# Board3.net
KiCad netlist of a schematic drawn in Altium Designer
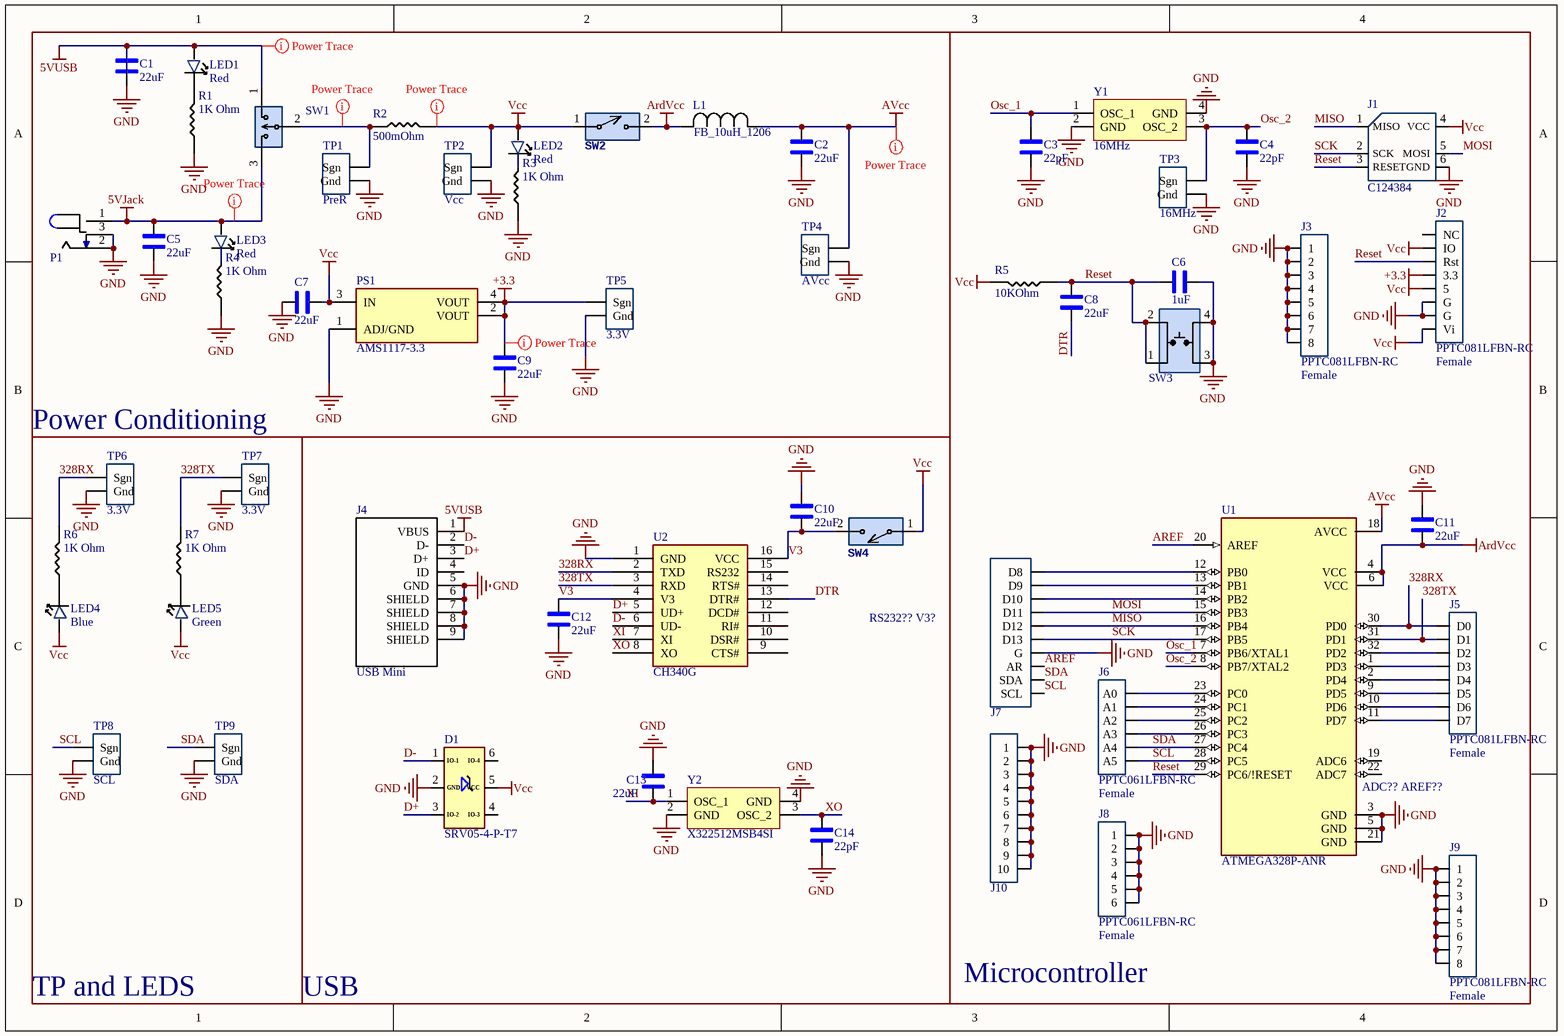
[diagram p0: Board3.SchDoc]

(export (version "E")
  (design (tool "Eeschema 10.0.6"))
  (components
    (comp (ref "C1")
      (value "22uF")
      (footprint "1206_Passive_Capacitor")
      (description "22uF ±10% 25V X5R 1206 Multilayer Ceramic Capacitors MLCC - SMD/SMT RoHS")
      (fields (field (name "MFR PART #") "CL31A226KAHNNNE") (field (name "LCSC PART#") "C12891"))
      (libsource (lib "ECEN5730Lib_2023_01_DS") (part "C_22uF_1206"))
    )
    (comp (ref "C2")
      (value "22uF")
      (footprint "1206_Passive_Capacitor")
      (description "22uF ±10% 25V X5R 1206 Multilayer Ceramic Capacitors MLCC - SMD/SMT RoHS")
      (fields (field (name "MFR PART #") "CL31A226KAHNNNE") (field (name "LCSC PART#") "C12891"))
      (libsource (lib "ECEN5730Lib_2023_01_DS") (part "C_22uF_1206"))
    )
    (comp (ref "C3")
      (value "22pF")
      (footprint "1206_Passive_Capacitor")
      (description "22pF ±5% 1kV C0G 1206 Multilayer Ceramic Capacitors MLCC - SMD/SMT RoHS")
      (fields (field (name "LCSC PART#") "C313096") (field (name "MFR PART #") "1206CG220J102NT"))
      (libsource (lib "ECEN5730Lib_2023_01_DS") (part "C_22pF_1206"))
    )
    (comp (ref "C4")
      (value "22pF")
      (footprint "1206_Passive_Capacitor")
      (description "22pF ±5% 1kV C0G 1206 Multilayer Ceramic Capacitors MLCC - SMD/SMT RoHS")
      (fields (field (name "LCSC PART#") "C313096") (field (name "MFR PART #") "1206CG220J102NT"))
      (libsource (lib "ECEN5730Lib_2023_01_DS") (part "C_22pF_1206"))
    )
    (comp (ref "C5")
      (value "22uF")
      (footprint "1206_Passive_Capacitor")
      (description "22uF ±10% 25V X5R 1206 Multilayer Ceramic Capacitors MLCC - SMD/SMT RoHS")
      (fields (field (name "MFR PART #") "CL31A226KAHNNNE") (field (name "LCSC PART#") "C12891"))
      (libsource (lib "ECEN5730Lib_2023_01_DS") (part "C_22uF_1206"))
    )
    (comp (ref "C6")
      (value "1uF")
      (footprint "1206_Passive_Capacitor")
      (description "MULTILAYER CERAMIC CAPACITORS MLCC - SMD/SMT 1UF 50V 1206 ROHS")
      (fields (field (name "MFR PART #") "CL31B105KBHNNNE") (field (name "LCSC PART#") "C1848"))
      (libsource (lib "ECEN5730Lib_2023_01_DS") (part "C_1uF_1206"))
    )
    (comp (ref "C7")
      (value "22uF")
      (footprint "1206_Passive_Capacitor")
      (description "22uF ±10% 25V X5R 1206 Multilayer Ceramic Capacitors MLCC - SMD/SMT RoHS")
      (fields (field (name "MFR PART #") "CL31A226KAHNNNE") (field (name "LCSC PART#") "C12891"))
      (libsource (lib "ECEN5730Lib_2023_01_DS") (part "C_22uF_1206"))
    )
    (comp (ref "C8")
      (value "22uF")
      (footprint "1206_Passive_Capacitor")
      (description "22uF ±10% 25V X5R 1206 Multilayer Ceramic Capacitors MLCC - SMD/SMT RoHS")
      (fields (field (name "MFR PART #") "CL31A226KAHNNNE") (field (name "LCSC PART#") "C12891"))
      (libsource (lib "ECEN5730Lib_2023_01_DS") (part "C_22uF_1206"))
    )
    (comp (ref "C9")
      (value "22uF")
      (footprint "1206_Passive_Capacitor")
      (description "22uF ±10% 25V X5R 1206 Multilayer Ceramic Capacitors MLCC - SMD/SMT RoHS")
      (fields (field (name "MFR PART #") "CL31A226KAHNNNE") (field (name "LCSC PART#") "C12891"))
      (libsource (lib "ECEN5730Lib_2023_01_DS") (part "C_22uF_1206"))
    )
    (comp (ref "C10")
      (value "22uF")
      (footprint "1206_Passive_Capacitor")
      (description "22uF ±10% 25V X5R 1206 Multilayer Ceramic Capacitors MLCC - SMD/SMT RoHS")
      (fields (field (name "MFR PART #") "CL31A226KAHNNNE") (field (name "LCSC PART#") "C12891"))
      (libsource (lib "ECEN5730Lib_2023_01_DS") (part "C_22uF_1206"))
    )
    (comp (ref "C11")
      (value "22uF")
      (footprint "1206_Passive_Capacitor")
      (description "22uF ±10% 25V X5R 1206 Multilayer Ceramic Capacitors MLCC - SMD/SMT RoHS")
      (fields (field (name "MFR PART #") "CL31A226KAHNNNE") (field (name "LCSC PART#") "C12891"))
      (libsource (lib "ECEN5730Lib_2023_01_DS") (part "C_22uF_1206"))
    )
    (comp (ref "C12")
      (value "22uF")
      (footprint "1206_Passive_Capacitor")
      (description "22uF ±10% 25V X5R 1206 Multilayer Ceramic Capacitors MLCC - SMD/SMT RoHS")
      (fields (field (name "MFR PART #") "CL31A226KAHNNNE") (field (name "LCSC PART#") "C12891"))
      (libsource (lib "ECEN5730Lib_2023_01_DS") (part "C_22uF_1206"))
    )
    (comp (ref "C13")
      (value "22uF")
      (footprint "1206_Passive_Capacitor")
      (description "22uF ±10% 25V X5R 1206 Multilayer Ceramic Capacitors MLCC - SMD/SMT RoHS")
      (fields (field (name "MFR PART #") "CL31A226KAHNNNE") (field (name "LCSC PART#") "C12891"))
      (libsource (lib "ECEN5730Lib_2023_01_DS") (part "C_22uF_1206"))
    )
    (comp (ref "C14")
      (value "22pF")
      (footprint "1206_Passive_Capacitor")
      (description "22pF ±5% 1kV C0G 1206 Multilayer Ceramic Capacitors MLCC - SMD/SMT RoHS")
      (fields (field (name "LCSC PART#") "C313096") (field (name "MFR PART #") "1206CG220J102NT"))
      (libsource (lib "ECEN5730Lib_2023_01_DS") (part "C_22pF_1206"))
    )
    (comp (ref "D1")
      (value "SRV05-4-P-T7")
      (footprint "TVS")
      (description "TVS SOT-23-6 ROHS")
      (fields (field (name "LCSC PART#") "C85364"))
      (libsource (lib "ECEN5730Lib_2023_01_DS") (part "D_TVS_Diode"))
    )
    (comp (ref "J1")
      (value "NRPN032PAEN-RC")
      (footprint "ICSP")
      (description "Connector Header Through Hole 6 position 0.079\" (2.00mm)")
      (fields (field (name "LCSC PART#") "C124384"))
      (libsource (lib "ECEN5730Lib_2023_01_DS") (part "J_ICSP"))
    )
    (comp (ref "J2")
      (value "PPTC081LFBN-RC")
      (footprint "8_PIN_ARD-PWR_100MIL")
      (description "8 Position Header Connector 0.100\" (2.54mm) Through Hole Tin")
      (fields (field (name "LCSC PART#") "C27438") (field (name "ALTIUM_VALUE") "Female"))
      (libsource (lib "ECEN5730Lib_2023_01_DS") (part "JF_8_PIN_FEMALE_ARD-Pwr"))
    )
    (comp (ref "J3")
      (value "PPTC081LFBN-RC")
      (footprint "8_PIN_100MIL - Female")
      (description "8 Position Header Connector 0.100\" (2.54mm) Through Hole Tin")
      (fields (field (name "LCSC PART#") "C27438") (field (name "ALTIUM_VALUE") "Female"))
      (libsource (lib "ECEN5730Lib_2023_01_DS") (part "JF_8_PIN_FEMALE"))
    )
    (comp (ref "J4")
      (value "USB Mini")
      (footprint "USB_MINI_B")
      (description "Through Hole USB Connectors RoHS")
      (fields (field (name "LCSC PART#") "C46398") (field (name "MFR PART #") "920-462A2021D10102"))
      (libsource (lib "ECEN5730Lib_2023_01_DS") (part "J_USB_B_Mini"))
    )
    (comp (ref "J5")
      (value "PPTC081LFBN-RC")
      (footprint "8_PIN_ARD-DIG_100MIL")
      (description "8 Position Header Connector 0.100\" (2.54mm) Through Hole Tin")
      (fields (field (name "LCSC PART#") "C27438") (field (name "ALTIUM_VALUE") "Female"))
      (libsource (lib "ECEN5730Lib_2023_01_DS") (part "JF_8_PIN_FEMALE_ARD-Dig"))
    )
    (comp (ref "J6")
      (value "PPTC061LFBN-RC")
      (footprint "6_PIN_ARD-Analog_100mil")
      (description "6 Position Header Connector 0.100\" (2.54mm) Through Hole Tin")
      (fields (field (name "LCSC PART#") "C40877") (field (name "ALTIUM_VALUE") "Female"))
      (libsource (lib "ECEN5730Lib_2023_01_DS") (part "JF_6_PIN_FEMALE_ARD-Anolog"))
    )
    (comp (ref "J7")
      (value "PPTC101LFBN-RC")
      (footprint "10_PIN_ARDUINO_100MIL")
      (description "10 Position Header Connector 0.100\" (2.54mm) Through Hole Tin")
      (fields (field (name "LCSC PART#") "C225507"))
      (libsource (lib "ECEN5730Lib_2023_01_DS") (part "JF_10_PIN_FEMALE_ARDUINO"))
    )
    (comp (ref "J8")
      (value "PPTC061LFBN-RC")
      (footprint "6_PIN_100MIL -Female")
      (description "6 Position Header Connector 0.100\" (2.54mm) Through Hole Tin")
      (fields (field (name "LCSC PART#") "C40877") (field (name "ALTIUM_VALUE") "Female"))
      (libsource (lib "ECEN5730Lib_2023_01_DS") (part "JF_6_PIN_FEMALE"))
    )
    (comp (ref "J9")
      (value "PPTC081LFBN-RC")
      (footprint "8_PIN_100MIL - Female")
      (description "8 Position Header Connector 0.100\" (2.54mm) Through Hole Tin")
      (fields (field (name "LCSC PART#") "C27438") (field (name "ALTIUM_VALUE") "Female"))
      (libsource (lib "ECEN5730Lib_2023_01_DS") (part "JF_8_PIN_FEMALE"))
    )
    (comp (ref "J10")
      (value "PPTC101LFBN-RC")
      (footprint "10_PIN_100MIL - Female")
      (description "10 Position Header Connector 0.100\" (2.54mm) Through Hole Tin")
      (fields (field (name "LCSC PART#") "C225507"))
      (libsource (lib "ECEN5730Lib_2023_01_DS") (part "JF_10_PIN_FEMALE_"))
    )
    (comp (ref "L1")
      (value "FB_10uH_1206")
      (footprint "AIML-1206_ABR-M")
      (description "25mA 10uH ±10% 800mΩ 1206  Inductors (SMD) ROHS")
      (fields (field (name "MFR PART #") "CMI321609X100KT") (field (name "LCSC PART#") "C1051"))
      (libsource (lib "ECEN5730Lib_2023_01_DS") (part "FB_10uH_1206"))
    )
    (comp (ref "LED1")
      (value "Red")
      (footprint "LED_1206")
      (description "Red 621~631nm 1206 Light Emitting Diodes (LED) RoHS")
      (fields (field (name "MFR PART #") "15-21/R6C-FQ1R1B/2T") (field (name "LCSC PART#") "C93133"))
      (libsource (lib "ECEN5730Lib_2023_01_DS") (part "LED_RED_1206"))
    )
    (comp (ref "LED2")
      (value "Red")
      (footprint "LED_1206")
      (description "Red 621~631nm 1206 Light Emitting Diodes (LED) RoHS")
      (fields (field (name "MFR PART #") "15-21/R6C-FQ1R1B/2T") (field (name "LCSC PART#") "C93133"))
      (libsource (lib "ECEN5730Lib_2023_01_DS") (part "LED_RED_1206"))
    )
    (comp (ref "LED3")
      (value "Red")
      (footprint "LED_1206")
      (description "Red 621~631nm 1206 Light Emitting Diodes (LED) RoHS")
      (fields (field (name "MFR PART #") "15-21/R6C-FQ1R1B/2T") (field (name "LCSC PART#") "C93133"))
      (libsource (lib "ECEN5730Lib_2023_01_DS") (part "LED_RED_1206"))
    )
    (comp (ref "LED4")
      (value "Blue")
      (footprint "LED_1206")
      (description "blue 1206  Light Emitting Diodes (LED) ROHS")
      (fields (field (name "MFR PART #") "NCD1206B1") (field (name "LCSC PART#") "C130717"))
      (libsource (lib "ECEN5730Lib_2023_01_DS") (part "LED_BLUE_1206"))
    )
    (comp (ref "LED5")
      (value "Green")
      (footprint "LED_1206")
      (description "Green 513~528nm 1206 Light Emitting Diodes (LED) RoHS")
      (fields (field (name "MFR PART #") "SZYY1206G") (field (name "LCSC PART#") "C434439"))
      (libsource (lib "ECEN5730Lib_2023_01_DS") (part "LED_GREEN_1206"))
    )
    (comp (ref "P1")
      (value "Power Jack")
      (footprint "Power_Jack")
      (description "Power Barrel Connector Jack 2.10mm ID (0.083\"), 5.50mm OD (0.217\") Through Hole, Right Angle")
      (fields (field (name "MFR PART #") "PJ-102A") (field (name "LCSC PART#") "C136744"))
      (libsource (lib "ECEN5730Lib_2023_01_DS") (part "P_Power Jack"))
    )
    (comp (ref "PS1")
      (value "AMS1117-3.3")
      (footprint "LDO")
      (description "LOW DROPOUT REGULATORS(LDO) POSITIVE FIXED 1.3V @ 800MA 15V 3.3V 1A SOT-223 ROHS")
      (fields (field (name "LCSC PART#") "C6186"))
      (libsource (lib "ECEN5730Lib_2023_01_DS") (part "PS_AMS_LDO_3v3"))
    )
    (comp (ref "R1")
      (value "1K Ohm")
      (footprint "1206_Passive_Resitor")
      (description "CHIP RESISTOR - SURFACE MOUNT 1KOHMS ±1% 1/4W 1206 ROHS")
      (fields (field (name "MFR PART #") "RNCP1206FTD1K00CT") (field (name "LCSC PART#") "C4410"))
      (libsource (lib "ECEN5730Lib_2023_01_DS") (part "R_1K_1206"))
    )
    (comp (ref "R2")
      (value "500mOhm")
      (footprint "1206_Passive_Resitor")
      (description "Resistors/Shunt 250mW 500mΩ ±800ppm/℃ ±5% 1206  Current Sense  Resistors ROHS")
      (fields (field (name "MFR PART #") "1206W4J050KT5E") (field (name "LCSC PART#") "C247433"))
      (libsource (lib "ECEN5730Lib_2023_01_DS") (part "R_500mOhm_1206"))
    )
    (comp (ref "R3")
      (value "1K Ohm")
      (footprint "1206_Passive_Resitor")
      (description "CHIP RESISTOR - SURFACE MOUNT 1KOHMS ±1% 1/4W 1206 ROHS")
      (fields (field (name "MFR PART #") "RNCP1206FTD1K00CT") (field (name "LCSC PART#") "C4410"))
      (libsource (lib "ECEN5730Lib_2023_01_DS") (part "R_1K_1206"))
    )
    (comp (ref "R4")
      (value "1K Ohm")
      (footprint "1206_Passive_Resitor")
      (description "CHIP RESISTOR - SURFACE MOUNT 1KOHMS ±1% 1/4W 1206 ROHS")
      (fields (field (name "MFR PART #") "RNCP1206FTD1K00CT") (field (name "LCSC PART#") "C4410"))
      (libsource (lib "ECEN5730Lib_2023_01_DS") (part "R_1K_1206"))
    )
    (comp (ref "R5")
      (value "10KOhm")
      (footprint "1206_Passive_Resitor")
      (description "10 kOhms ±5% 0.25W, 1/4W Chip Resistor 1206 (3216 Metric) Automotive AEC-Q200 Thick Film")
      (fields (field (name "MFR PART #") "RMCF1206FT10K0") (field (name "LCSC PART#") "C17902"))
      (libsource (lib "ECEN5730Lib_2023_01_DS") (part "R_10KOhm_1206"))
    )
    (comp (ref "R6")
      (value "1K Ohm")
      (footprint "1206_Passive_Resitor")
      (description "CHIP RESISTOR - SURFACE MOUNT 1KOHMS ±1% 1/4W 1206 ROHS")
      (fields (field (name "MFR PART #") "RNCP1206FTD1K00CT") (field (name "LCSC PART#") "C4410"))
      (libsource (lib "ECEN5730Lib_2023_01_DS") (part "R_1K_1206"))
    )
    (comp (ref "R7")
      (value "1K Ohm")
      (footprint "1206_Passive_Resitor")
      (description "CHIP RESISTOR - SURFACE MOUNT 1KOHMS ±1% 1/4W 1206 ROHS")
      (fields (field (name "MFR PART #") "RNCP1206FTD1K00CT") (field (name "LCSC PART#") "C4410"))
      (libsource (lib "ECEN5730Lib_2023_01_DS") (part "R_1K_1206"))
    )
    (comp (ref "SW1")
      (value "PREC003SAAN-RC")
      (footprint "3_PIN_100mil")
      (description "Connector Header Through Hole 3 position 0.100\" (2.54mm)")
      (fields (field (name "LCSC PART#") "C49257"))
      (libsource (lib "ECEN5730Lib_2023_01_DS") (part "SW_3Pin_100mil_Switch"))
    )
    (comp (ref "SW2")
      (value "SW_2Pin_100mil_Switch")
      (footprint "2Pin-Header-Conn")
      (description "2Pin Header")
      (fields (field (name "LCSC PART#") "C124375"))
      (libsource (lib "") (part "SW_2Pin_100mil_Switch_1"))
    )
    (comp (ref "SW3")
      (value "TL3305AF160QG")
      (footprint "Switch_JLC")
      (description "Tactile Switch SPST-NO Top Actuated Surface Mount")
      (fields (field (name "MFR PART #") "KH-4.5X4.5X4.3H-STM") (field (name "LCSC PART#") "C2837550"))
      (libsource (lib "ECEN5730Lib_2023_01_DS") (part "SW_Push_Button_JLC"))
    )
    (comp (ref "SW4")
      (value "SW_2Pin_100mil_Switch")
      (footprint "2Pin-Header-Conn")
      (description "2Pin Header")
      (fields (field (name "LCSC PART#") "C124375"))
      (libsource (lib "ECEN5730Lib_2023_01_DS") (part "SW_2Pin_100mil_Switch"))
    )
    (comp (ref "TP1")
      (value "PreR")
      (footprint "TP10x_Probe")
      (description "Test Point 300 mil centers")
      (libsource (lib "ECEN5730Lib_2023_01_DS") (part "TP_10x_Probe"))
    )
    (comp (ref "TP2")
      (value "Vcc")
      (footprint "TP10x_Probe")
      (description "Test Point 300 mil centers")
      (libsource (lib "ECEN5730Lib_2023_01_DS") (part "TP_10x_Probe"))
    )
    (comp (ref "TP3")
      (value "16MHz")
      (footprint "TP10x_Probe")
      (description "Test Point 300 mil centers")
      (libsource (lib "ECEN5730Lib_2023_01_DS") (part "TP_10x_Probe"))
    )
    (comp (ref "TP4")
      (value "AVcc")
      (footprint "TP10x_Probe")
      (description "Test Point 300 mil centers")
      (libsource (lib "ECEN5730Lib_2023_01_DS") (part "TP_10x_Probe"))
    )
    (comp (ref "TP5")
      (value "3.3V")
      (footprint "TP10x_Probe")
      (description "Test Point 300 mil centers")
      (libsource (lib "") (part "TP_10x_Probe_1"))
    )
    (comp (ref "TP6")
      (value "3.3V")
      (footprint "TP10x_Probe")
      (description "Test Point 300 mil centers")
      (libsource (lib "") (part "TP_10x_Probe_1"))
    )
    (comp (ref "TP7")
      (value "3.3V")
      (footprint "TP10x_Probe")
      (description "Test Point 300 mil centers")
      (libsource (lib "") (part "TP_10x_Probe_1"))
    )
    (comp (ref "TP8")
      (value "SCL")
      (footprint "TP10x_Probe")
      (description "Test Point 300 mil centers")
      (libsource (lib "") (part "TP_10x_Probe_1"))
    )
    (comp (ref "TP9")
      (value "SDA")
      (footprint "TP10x_Probe")
      (description "Test Point 300 mil centers")
      (libsource (lib "") (part "TP_10x_Probe_1"))
    )
    (comp (ref "U1")
      (value "ATMEGA328P-ANR")
      (footprint "ATMega328P")
      (description "AVR AVR® ATmega Microcontroller IC 8-Bit 20MHz 32KB (16K x 16) FLASH 32-TQFP (7x7)")
      (fields (field (name "MFR PART #") "ATMEGA328P-AU") (field (name "LCSC PART#") "C14877"))
      (libsource (lib "ECEN5730Lib_2023_01_DS") (part "U_ATMega328P"))
    )
    (comp (ref "U2")
      (value "CH340G")
      (footprint "USB to serial")
      (description "Transceiver USB 2.0 2Mbps SOP-16_150mil USB ICs RoHS")
      (fields (field (name "LCSC PART#") "C14267"))
      (libsource (lib "ECEN5730Lib_2023_01_DS") (part "U_USBtoSerial"))
    )
    (comp (ref "Y1")
      (value "16MHz")
      (footprint "Crystal resonator")
      (description "±10ppm 16000000Hz -40℃~85℃ 贴片无源晶振 60Ω 9pF SMD3225-4P Crystals ROHS")
      (fields (field (name "LCSC PART#") "C13738") (field (name "MFR PART #") "X322516MLB4SI"))
      (libsource (lib "ECEN5730Lib_2023_01_DS") (part "X_16Mhz_Res"))
    )
    (comp (ref "Y2")
      (value "X322512MSB4SI")
      (footprint "Crystal resonator")
      (description "SMD Crystal Resonators 12MHz ±10ppm SMD-3225_4P RoHS")
      (fields (field (name "LCSC PART#") "C9002"))
      (libsource (lib "ECEN5730Lib_2023_01_DS") (part "X_12MHz_Res"))
    )
  )
  (nets
    (net (code "1") (name "+3.3") (class "Default")
      (node (ref "C9") (pin "2") (pinfunction "2_2") (pintype "passive"))
      (node (ref "J2") (pin "4") (pinfunction "3.3_4") (pintype "passive"))
      (node (ref "PS1") (pin "2") (pinfunction "VOUT_2") (pintype "power_in"))
      (node (ref "PS1") (pin "4") (pinfunction "VOUT_4") (pintype "power_in"))
      (node (ref "TP5") (pin "1") (pinfunction "Sgn_1") (pintype "passive"))
    )
    (net (code "2") (name "/328RX") (class "Default")
      (node (ref "J5") (pin "8") (pinfunction "D0_8") (pintype "passive"))
      (node (ref "R6") (pin "2") (pinfunction "2_2") (pintype "passive"))
      (node (ref "TP6") (pin "1") (pinfunction "Sgn_1") (pintype "passive"))
      (node (ref "U1") (pin "30") (pinfunction "PD0_30") (pintype "bidirectional"))
      (node (ref "U2") (pin "2") (pinfunction "TXD_2") (pintype "passive"))
    )
    (net (code "3") (name "/328TX") (class "Default")
      (node (ref "J5") (pin "7") (pinfunction "D1_7") (pintype "passive"))
      (node (ref "R7") (pin "2") (pinfunction "2_2") (pintype "passive"))
      (node (ref "TP7") (pin "1") (pinfunction "Sgn_1") (pintype "passive"))
      (node (ref "U1") (pin "31") (pinfunction "PD1_31") (pintype "bidirectional"))
      (node (ref "U2") (pin "3") (pinfunction "RXD_3") (pintype "passive"))
    )
    (net (code "4") (name "/AREF") (class "Default")
      (node (ref "J7") (pin "3") (pinfunction "AR_3") (pintype "passive"))
      (node (ref "U1") (pin "20") (pinfunction "AREF_20") (pintype "input"))
    )
    (net (code "5") (name "/D+") (class "Default")
      (node (ref "D1") (pin "3") (pinfunction "IO-2_3") (pintype "passive"))
      (node (ref "J4") (pin "3") (pinfunction "D+_3") (pintype "passive"))
      (node (ref "U2") (pin "5") (pinfunction "UD+_5") (pintype "passive"))
    )
    (net (code "6") (name "/D-") (class "Default")
      (node (ref "D1") (pin "1") (pinfunction "IO-1_1") (pintype "passive"))
      (node (ref "J4") (pin "2") (pinfunction "D-_2") (pintype "passive"))
      (node (ref "U2") (pin "6") (pinfunction "UD-_6") (pintype "passive"))
    )
    (net (code "7") (name "/DTR") (class "Default")
      (node (ref "C8") (pin "2") (pinfunction "2_2") (pintype "passive"))
      (node (ref "U2") (pin "13") (pinfunction "DTR#_13") (pintype "passive"))
    )
    (net (code "8") (name "/MISO") (class "Default")
      (node (ref "J1") (pin "1") (pinfunction "MISO_1") (pintype "passive"))
      (node (ref "J7") (pin "6") (pinfunction "D12_6") (pintype "passive"))
      (node (ref "U1") (pin "16") (pinfunction "PB4_16") (pintype "bidirectional"))
    )
    (net (code "9") (name "/MOSI") (class "Default")
      (node (ref "J1") (pin "5") (pinfunction "MOSI_5") (pintype "passive"))
      (node (ref "J7") (pin "7") (pinfunction "D11_7") (pintype "passive"))
      (node (ref "U1") (pin "15") (pinfunction "PB3_15") (pintype "bidirectional"))
    )
    (net (code "10") (name "/Osc_1") (class "Default")
      (node (ref "C3") (pin "2") (pinfunction "2_2") (pintype "passive"))
      (node (ref "U1") (pin "7") (pinfunction "PB6/XTAL1_7") (pintype "bidirectional"))
      (node (ref "Y1") (pin "1") (pinfunction "OSC_1_1") (pintype "passive"))
    )
    (net (code "11") (name "/Osc_2") (class "Default")
      (node (ref "C4") (pin "2") (pinfunction "2_2") (pintype "passive"))
      (node (ref "TP3") (pin "1") (pinfunction "Sgn_1") (pintype "passive"))
      (node (ref "U1") (pin "8") (pinfunction "PB7/XTAL2_8") (pintype "bidirectional"))
      (node (ref "Y1") (pin "3") (pinfunction "OSC_2_3") (pintype "passive"))
    )
    (net (code "12") (name "/Reset") (class "Default")
      (node (ref "C6") (pin "2") (pinfunction "2_2") (pintype "passive"))
      (node (ref "C8") (pin "1") (pinfunction "1_1") (pintype "passive"))
      (node (ref "J1") (pin "3") (pinfunction "RESET_3") (pintype "passive"))
      (node (ref "J2") (pin "3") (pinfunction "Rst_3") (pintype "passive"))
      (node (ref "R5") (pin "1") (pinfunction "1_1") (pintype "passive"))
      (node (ref "SW3") (pin "1") (pinfunction "1_1") (pintype "passive"))
      (node (ref "SW3") (pin "2") (pinfunction "2_2") (pintype "passive"))
      (node (ref "U1") (pin "29") (pinfunction "PC6/!RESET_29") (pintype "bidirectional"))
    )
    (net (code "13") (name "/SCK") (class "Default")
      (node (ref "J1") (pin "2") (pinfunction "SCK_2") (pintype "passive"))
      (node (ref "J7") (pin "5") (pinfunction "D13_5") (pintype "passive"))
      (node (ref "U1") (pin "17") (pinfunction "PB5_17") (pintype "bidirectional"))
    )
    (net (code "14") (name "/SCL") (class "Default")
      (node (ref "J6") (pin "6") (pinfunction "A5_6") (pintype "passive"))
      (node (ref "J7") (pin "1") (pinfunction "SCL_1") (pintype "passive"))
      (node (ref "TP8") (pin "1") (pinfunction "Sgn_1") (pintype "passive"))
      (node (ref "U1") (pin "28") (pinfunction "PC5_28") (pintype "bidirectional"))
    )
    (net (code "15") (name "/SDA") (class "Default")
      (node (ref "J6") (pin "5") (pinfunction "A4_5") (pintype "passive"))
      (node (ref "J7") (pin "2") (pinfunction "SDA_2") (pintype "passive"))
      (node (ref "TP9") (pin "1") (pinfunction "Sgn_1") (pintype "passive"))
      (node (ref "U1") (pin "27") (pinfunction "PC4_27") (pintype "bidirectional"))
    )
    (net (code "16") (name "/V3") (class "Default")
      (node (ref "C10") (pin "2") (pinfunction "2_2") (pintype "passive"))
      (node (ref "C12") (pin "2") (pinfunction "2_2") (pintype "passive"))
      (node (ref "SW4") (pin "2") (pinfunction "2_2") (pintype "passive"))
      (node (ref "U2") (pin "16") (pinfunction "VCC_16") (pintype "passive"))
      (node (ref "U2") (pin "4") (pinfunction "V3_4") (pintype "passive"))
    )
    (net (code "17") (name "/XI") (class "Default")
      (node (ref "C13") (pin "1") (pinfunction "1_1") (pintype "passive"))
      (node (ref "U2") (pin "7") (pinfunction "XI_7") (pintype "passive"))
      (node (ref "Y2") (pin "1") (pinfunction "OSC_1_1") (pintype "passive"))
    )
    (net (code "18") (name "/XO") (class "Default")
      (node (ref "C14") (pin "2") (pinfunction "2_2") (pintype "passive"))
      (node (ref "U2") (pin "8") (pinfunction "XO_8") (pintype "passive"))
      (node (ref "Y2") (pin "3") (pinfunction "OSC_2_3") (pintype "passive"))
    )
    (net (code "19") (name "5VJack") (class "Default")
      (node (ref "C5") (pin "2") (pinfunction "2_2") (pintype "passive"))
      (node (ref "LED3") (pin "1") (pinfunction "1_1") (pintype "passive"))
      (node (ref "P1") (pin "1") (pinfunction "1_1") (pintype "power_in"))
      (node (ref "SW1") (pin "3") (pinfunction "3_3") (pintype "passive"))
    )
    (net (code "20") (name "5VUSB") (class "Default")
      (node (ref "C1") (pin "1") (pinfunction "1_1") (pintype "passive"))
      (node (ref "J4") (pin "1") (pinfunction "VBUS_1") (pintype "passive"))
      (node (ref "LED1") (pin "1") (pinfunction "1_1") (pintype "passive"))
      (node (ref "SW1") (pin "1") (pinfunction "1_1") (pintype "passive"))
    )
    (net (code "21") (name "AVcc") (class "Default")
      (node (ref "C2") (pin "2") (pinfunction "2_2") (pintype "passive"))
      (node (ref "L1") (pin "1") (pinfunction "1_1") (pintype "passive"))
      (node (ref "TP4") (pin "1") (pinfunction "Sgn_1") (pintype "passive"))
      (node (ref "U1") (pin "18") (pinfunction "AVCC_18") (pintype "power_in"))
    )
    (net (code "22") (name "ArdVcc") (class "Default")
      (node (ref "C11") (pin "2") (pinfunction "2_2") (pintype "passive"))
      (node (ref "L1") (pin "2") (pinfunction "2_2") (pintype "passive"))
      (node (ref "SW2") (pin "2") (pinfunction "2_2") (pintype "passive"))
      (node (ref "U1") (pin "4") (pinfunction "VCC_4") (pintype "power_in"))
      (node (ref "U1") (pin "6") (pinfunction "VCC_6") (pintype "power_in"))
    )
    (net (code "23") (name "GND") (class "Default")
      (node (ref "C1") (pin "2") (pinfunction "2_2") (pintype "passive"))
      (node (ref "C10") (pin "1") (pinfunction "1_1") (pintype "passive"))
      (node (ref "C11") (pin "1") (pinfunction "1_1") (pintype "passive"))
      (node (ref "C12") (pin "1") (pinfunction "1_1") (pintype "passive"))
      (node (ref "C13") (pin "2") (pinfunction "2_2") (pintype "passive"))
      (node (ref "C14") (pin "1") (pinfunction "1_1") (pintype "passive"))
      (node (ref "C2") (pin "1") (pinfunction "1_1") (pintype "passive"))
      (node (ref "C3") (pin "1") (pinfunction "1_1") (pintype "passive"))
      (node (ref "C4") (pin "1") (pinfunction "1_1") (pintype "passive"))
      (node (ref "C5") (pin "1") (pinfunction "1_1") (pintype "passive"))
      (node (ref "C6") (pin "1") (pinfunction "1_1") (pintype "passive"))
      (node (ref "C7") (pin "1") (pinfunction "1_1") (pintype "passive"))
      (node (ref "C9") (pin "1") (pinfunction "1_1") (pintype "passive"))
      (node (ref "D1") (pin "2") (pinfunction "GND_2") (pintype "passive"))
      (node (ref "J1") (pin "6") (pinfunction "GND_6") (pintype "passive"))
      (node (ref "J10") (pin "1") (pinfunction "1_1") (pintype "passive"))
      (node (ref "J10") (pin "10") (pinfunction "10_10") (pintype "passive"))
      (node (ref "J10") (pin "2") (pinfunction "2_2") (pintype "passive"))
      (node (ref "J10") (pin "3") (pinfunction "3_3") (pintype "passive"))
      (node (ref "J10") (pin "4") (pinfunction "4_4") (pintype "passive"))
      (node (ref "J10") (pin "5") (pinfunction "5_5") (pintype "passive"))
      (node (ref "J10") (pin "6") (pinfunction "6_6") (pintype "passive"))
      (node (ref "J10") (pin "7") (pinfunction "7_7") (pintype "passive"))
      (node (ref "J10") (pin "8") (pinfunction "8_8") (pintype "passive"))
      (node (ref "J10") (pin "9") (pinfunction "9_9") (pintype "passive"))
      (node (ref "J2") (pin "6") (pinfunction "G_6") (pintype "passive"))
      (node (ref "J2") (pin "7") (pinfunction "G_7") (pintype "passive"))
      (node (ref "J3") (pin "1") (pinfunction "1_1") (pintype "passive"))
      (node (ref "J3") (pin "2") (pinfunction "2_2") (pintype "passive"))
      (node (ref "J3") (pin "3") (pinfunction "3_3") (pintype "passive"))
      (node (ref "J3") (pin "4") (pinfunction "4_4") (pintype "passive"))
      (node (ref "J3") (pin "5") (pinfunction "5_5") (pintype "passive"))
      (node (ref "J3") (pin "6") (pinfunction "6_6") (pintype "passive"))
      (node (ref "J3") (pin "7") (pinfunction "7_7") (pintype "passive"))
      (node (ref "J3") (pin "8") (pinfunction "8_8") (pintype "passive"))
      (node (ref "J4") (pin "5") (pinfunction "GND_5") (pintype "passive"))
      (node (ref "J4") (pin "6") (pinfunction "SHIELD_6") (pintype "passive"))
      (node (ref "J4") (pin "7") (pinfunction "SHIELD_7") (pintype "passive"))
      (node (ref "J4") (pin "8") (pinfunction "SHIELD_8") (pintype "passive"))
      (node (ref "J4") (pin "9") (pinfunction "SHIELD_9") (pintype "passive"))
      (node (ref "J7") (pin "4") (pinfunction "G_4") (pintype "passive"))
      (node (ref "J8") (pin "1") (pinfunction "1_1") (pintype "passive"))
      (node (ref "J8") (pin "2") (pinfunction "2_2") (pintype "passive"))
      (node (ref "J8") (pin "3") (pinfunction "3_3") (pintype "passive"))
      (node (ref "J8") (pin "4") (pinfunction "4_4") (pintype "passive"))
      (node (ref "J8") (pin "5") (pinfunction "5_5") (pintype "passive"))
      (node (ref "J8") (pin "6") (pinfunction "6_6") (pintype "passive"))
      (node (ref "J9") (pin "1") (pinfunction "1_1") (pintype "passive"))
      (node (ref "J9") (pin "2") (pinfunction "2_2") (pintype "passive"))
      (node (ref "J9") (pin "3") (pinfunction "3_3") (pintype "passive"))
      (node (ref "J9") (pin "4") (pinfunction "4_4") (pintype "passive"))
      (node (ref "J9") (pin "5") (pinfunction "5_5") (pintype "passive"))
      (node (ref "J9") (pin "6") (pinfunction "6_6") (pintype "passive"))
      (node (ref "J9") (pin "7") (pinfunction "7_7") (pintype "passive"))
      (node (ref "J9") (pin "8") (pinfunction "8_8") (pintype "passive"))
      (node (ref "P1") (pin "2") (pinfunction "2_2") (pintype "power_in"))
      (node (ref "P1") (pin "3") (pinfunction "3_3") (pintype "power_in"))
      (node (ref "PS1") (pin "1") (pinfunction "ADJ/GND_1") (pintype "passive"))
      (node (ref "R1") (pin "1") (pinfunction "1_1") (pintype "passive"))
      (node (ref "R3") (pin "1") (pinfunction "1_1") (pintype "passive"))
      (node (ref "R4") (pin "1") (pinfunction "1_1") (pintype "passive"))
      (node (ref "SW3") (pin "3") (pinfunction "3_3") (pintype "passive"))
      (node (ref "SW3") (pin "4") (pinfunction "4_4") (pintype "passive"))
      (node (ref "TP1") (pin "2") (pinfunction "Gnd_2") (pintype "passive"))
      (node (ref "TP2") (pin "2") (pinfunction "Gnd_2") (pintype "passive"))
      (node (ref "TP3") (pin "2") (pinfunction "Gnd_2") (pintype "passive"))
      (node (ref "TP4") (pin "2") (pinfunction "Gnd_2") (pintype "passive"))
      (node (ref "TP5") (pin "2") (pinfunction "Gnd_2") (pintype "passive"))
      (node (ref "TP6") (pin "2") (pinfunction "Gnd_2") (pintype "passive"))
      (node (ref "TP7") (pin "2") (pinfunction "Gnd_2") (pintype "passive"))
      (node (ref "TP8") (pin "2") (pinfunction "Gnd_2") (pintype "passive"))
      (node (ref "TP9") (pin "2") (pinfunction "Gnd_2") (pintype "passive"))
      (node (ref "U1") (pin "21") (pinfunction "GND_21") (pintype "power_in"))
      (node (ref "U1") (pin "3") (pinfunction "GND_3") (pintype "power_in"))
      (node (ref "U1") (pin "5") (pinfunction "GND_5") (pintype "power_in"))
      (node (ref "U2") (pin "1") (pinfunction "GND_1") (pintype "passive"))
      (node (ref "Y1") (pin "2") (pinfunction "GND_2") (pintype "passive"))
      (node (ref "Y1") (pin "4") (pinfunction "GND_4") (pintype "passive"))
      (node (ref "Y2") (pin "2") (pinfunction "GND_2") (pintype "passive"))
      (node (ref "Y2") (pin "4") (pinfunction "GND_4") (pintype "passive"))
    )
    (net (code "24") (name "Net-(J5-D2)") (class "Default")
      (node (ref "J5") (pin "6") (pinfunction "D2_6") (pintype "passive"))
      (node (ref "U1") (pin "32") (pinfunction "PD2_32") (pintype "bidirectional"))
    )
    (net (code "25") (name "Net-(J5-D3)") (class "Default")
      (node (ref "J5") (pin "5") (pinfunction "D3_5") (pintype "passive"))
      (node (ref "U1") (pin "1") (pinfunction "PD3_1") (pintype "bidirectional"))
    )
    (net (code "26") (name "Net-(J5-D4)") (class "Default")
      (node (ref "J5") (pin "4") (pinfunction "D4_4") (pintype "passive"))
      (node (ref "U1") (pin "2") (pinfunction "PD4_2") (pintype "bidirectional"))
    )
    (net (code "27") (name "Net-(J5-D5)") (class "Default")
      (node (ref "J5") (pin "3") (pinfunction "D5_3") (pintype "passive"))
      (node (ref "U1") (pin "9") (pinfunction "PD5_9") (pintype "bidirectional"))
    )
    (net (code "28") (name "Net-(J5-D6)") (class "Default")
      (node (ref "J5") (pin "2") (pinfunction "D6_2") (pintype "passive"))
      (node (ref "U1") (pin "10") (pinfunction "PD6_10") (pintype "bidirectional"))
    )
    (net (code "29") (name "Net-(J5-D7)") (class "Default")
      (node (ref "J5") (pin "1") (pinfunction "D7_1") (pintype "passive"))
      (node (ref "U1") (pin "11") (pinfunction "PD7_11") (pintype "bidirectional"))
    )
    (net (code "30") (name "Net-(J6-A0)") (class "Default")
      (node (ref "J6") (pin "1") (pinfunction "A0_1") (pintype "passive"))
      (node (ref "U1") (pin "23") (pinfunction "PC0_23") (pintype "bidirectional"))
    )
    (net (code "31") (name "Net-(J6-A1)") (class "Default")
      (node (ref "J6") (pin "2") (pinfunction "A1_2") (pintype "passive"))
      (node (ref "U1") (pin "24") (pinfunction "PC1_24") (pintype "bidirectional"))
    )
    (net (code "32") (name "Net-(J6-A2)") (class "Default")
      (node (ref "J6") (pin "3") (pinfunction "A2_3") (pintype "passive"))
      (node (ref "U1") (pin "25") (pinfunction "PC2_25") (pintype "bidirectional"))
    )
    (net (code "33") (name "Net-(J6-A3)") (class "Default")
      (node (ref "J6") (pin "4") (pinfunction "A3_4") (pintype "passive"))
      (node (ref "U1") (pin "26") (pinfunction "PC3_26") (pintype "bidirectional"))
    )
    (net (code "34") (name "Net-(J7-D8)") (class "Default")
      (node (ref "J7") (pin "10") (pinfunction "D8_10") (pintype "passive"))
      (node (ref "U1") (pin "12") (pinfunction "PB0_12") (pintype "bidirectional"))
    )
    (net (code "35") (name "Net-(J7-D9)") (class "Default")
      (node (ref "J7") (pin "9") (pinfunction "D9_9") (pintype "passive"))
      (node (ref "U1") (pin "13") (pinfunction "PB1_13") (pintype "bidirectional"))
    )
    (net (code "36") (name "Net-(J7-D10)") (class "Default")
      (node (ref "J7") (pin "8") (pinfunction "D10_8") (pintype "passive"))
      (node (ref "U1") (pin "14") (pinfunction "PB2_14") (pintype "bidirectional"))
    )
    (net (code "37") (name "Net-(LED1-Pad2)") (class "Default")
      (node (ref "LED1") (pin "2") (pinfunction "2_2") (pintype "passive"))
      (node (ref "R1") (pin "2") (pinfunction "2_2") (pintype "passive"))
    )
    (net (code "38") (name "Net-(LED2-Pad2)") (class "Default")
      (node (ref "LED2") (pin "2") (pinfunction "2_2") (pintype "passive"))
      (node (ref "R3") (pin "2") (pinfunction "2_2") (pintype "passive"))
    )
    (net (code "39") (name "Net-(LED3-Pad2)") (class "Default")
      (node (ref "LED3") (pin "2") (pinfunction "2_2") (pintype "passive"))
      (node (ref "R4") (pin "2") (pinfunction "2_2") (pintype "passive"))
    )
    (net (code "40") (name "Net-(LED4-Pad2)") (class "Default")
      (node (ref "LED4") (pin "2") (pinfunction "2_2") (pintype "passive"))
      (node (ref "R6") (pin "1") (pinfunction "1_1") (pintype "passive"))
    )
    (net (code "41") (name "Net-(LED5-Pad2)") (class "Default")
      (node (ref "LED5") (pin "2") (pinfunction "2_2") (pintype "passive"))
      (node (ref "R7") (pin "1") (pinfunction "1_1") (pintype "passive"))
    )
    (net (code "42") (name "Net-(TP1-Sgn)") (class "Default")
      (node (ref "R2") (pin "1") (pinfunction "1_1") (pintype "passive"))
      (node (ref "SW1") (pin "2") (pinfunction "2_2") (pintype "passive"))
      (node (ref "TP1") (pin "1") (pinfunction "Sgn_1") (pintype "passive"))
    )
    (net (code "43") (name "Vcc") (class "Default")
      (node (ref "C7") (pin "2") (pinfunction "2_2") (pintype "passive"))
      (node (ref "D1") (pin "5") (pinfunction "VCC_5") (pintype "passive"))
      (node (ref "J1") (pin "4") (pinfunction "VCC_4") (pintype "passive"))
      (node (ref "J2") (pin "2") (pinfunction "IO_2") (pintype "passive"))
      (node (ref "J2") (pin "5") (pinfunction "5_5") (pintype "passive"))
      (node (ref "J2") (pin "8") (pinfunction "Vi_8") (pintype "passive"))
      (node (ref "LED2") (pin "1") (pinfunction "1_1") (pintype "passive"))
      (node (ref "LED4") (pin "1") (pinfunction "1_1") (pintype "passive"))
      (node (ref "LED5") (pin "1") (pinfunction "1_1") (pintype "passive"))
      (node (ref "PS1") (pin "3") (pinfunction "IN_3") (pintype "power_in"))
      (node (ref "R2") (pin "2") (pinfunction "2_2") (pintype "passive"))
      (node (ref "R5") (pin "2") (pinfunction "2_2") (pintype "passive"))
      (node (ref "SW2") (pin "1") (pinfunction "1_1") (pintype "passive"))
      (node (ref "SW4") (pin "1") (pinfunction "1_1") (pintype "passive"))
      (node (ref "TP2") (pin "1") (pinfunction "Sgn_1") (pintype "passive"))
    )
    (net (code "44") (name "unconnected-(D1-IO-3-Pad4)") (class "Default")
      (node (ref "D1") (pin "4") (pinfunction "IO-3_4") (pintype "passive"))
    )
    (net (code "45") (name "unconnected-(D1-IO-4-Pad6)") (class "Default")
      (node (ref "D1") (pin "6") (pinfunction "IO-4_6") (pintype "passive"))
    )
    (net (code "46") (name "unconnected-(J2-NC-Pad1)") (class "Default")
      (node (ref "J2") (pin "1") (pinfunction "NC_1") (pintype "passive"))
    )
    (net (code "47") (name "unconnected-(J4-ID-Pad4)") (class "Default")
      (node (ref "J4") (pin "4") (pinfunction "ID_4") (pintype "passive"))
    )
    (net (code "48") (name "unconnected-(U1-ADC6-Pad19)") (class "Default")
      (node (ref "U1") (pin "19") (pinfunction "ADC6_19") (pintype "bidirectional"))
    )
    (net (code "49") (name "unconnected-(U1-ADC7-Pad22)") (class "Default")
      (node (ref "U1") (pin "22") (pinfunction "ADC7_22") (pintype "bidirectional"))
    )
    (net (code "50") (name "unconnected-(U2-CTS#-Pad9)") (class "Default")
      (node (ref "U2") (pin "9") (pinfunction "CTS#_9") (pintype "passive"))
    )
    (net (code "51") (name "unconnected-(U2-DCD#-Pad12)") (class "Default")
      (node (ref "U2") (pin "12") (pinfunction "DCD#_12") (pintype "passive"))
    )
    (net (code "52") (name "unconnected-(U2-DSR#-Pad10)") (class "Default")
      (node (ref "U2") (pin "10") (pinfunction "DSR#_10") (pintype "passive"))
    )
    (net (code "53") (name "unconnected-(U2-RI#-Pad11)") (class "Default")
      (node (ref "U2") (pin "11") (pinfunction "RI#_11") (pintype "passive"))
    )
    (net (code "54") (name "unconnected-(U2-RS232-Pad15)") (class "Default")
      (node (ref "U2") (pin "15") (pinfunction "RS232_15") (pintype "passive"))
    )
    (net (code "55") (name "unconnected-(U2-RTS#-Pad14)") (class "Default")
      (node (ref "U2") (pin "14") (pinfunction "RTS#_14") (pintype "passive"))
    )
  )
)
